# PCB_0_2.net
KiCad netlist of a schematic drawn in EAGLE
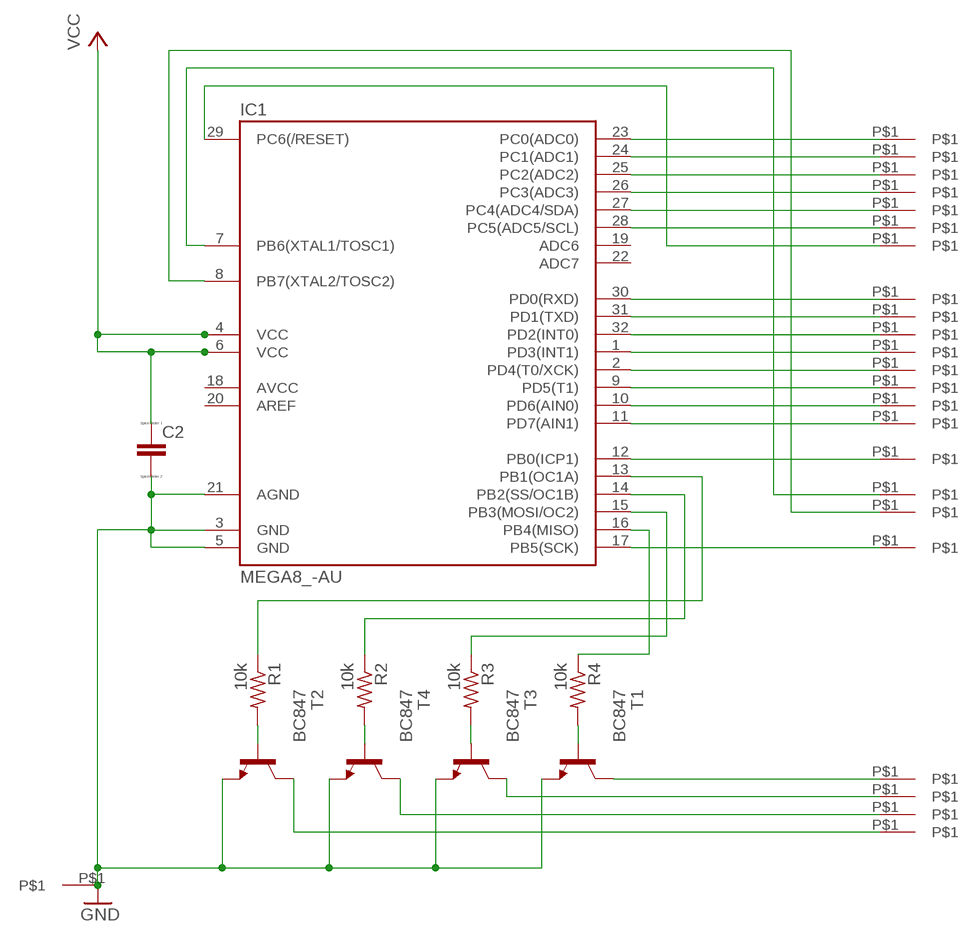
[diagram p0: schematic, sheet 1]

(export (version "E")
  (design (tool "Eeschema 10.0.6"))
  (components
    (comp (ref "C2")
      (value "C-EUC0603K")
      (footprint "eagle-import:C0603K")
      (libsource (lib "eagle-import") (part "C-EUC0603K"))
    )
    (comp (ref "IC1")
      (value "MEGA8_-AU")
      (footprint "eagle-import:TQFP32-08")
      (libsource (lib "eagle-import") (part "MEGA8_-AU"))
    )
    (comp (ref "PC0")
      (value "Fahrkanal")
      (footprint "eagle-import:PAD")
      (libsource (lib "eagle-import") (part "PAD"))
    )
    (comp (ref "PC1")
      (value "Fahrkanal")
      (footprint "eagle-import:PAD")
      (libsource (lib "eagle-import") (part "PAD"))
    )
    (comp (ref "PC2")
      (value "Fahrkanal")
      (footprint "eagle-import:PAD")
      (libsource (lib "eagle-import") (part "PAD"))
    )
    (comp (ref "PC3")
      (value "Fahrkanal")
      (footprint "eagle-import:PAD")
      (libsource (lib "eagle-import") (part "PAD"))
    )
    (comp (ref "PC4")
      (value "Fahrkanal")
      (footprint "eagle-import:PAD")
      (libsource (lib "eagle-import") (part "PAD"))
    )
    (comp (ref "PC5")
      (value "Fahrkanal")
      (footprint "eagle-import:PAD")
      (libsource (lib "eagle-import") (part "PAD"))
    )
    (comp (ref "R1")
      (value "10k")
      (footprint "eagle-import:R0402")
      (libsource (lib "eagle-import") (part "R-US_R0402"))
    )
    (comp (ref "R2")
      (value "10k")
      (footprint "eagle-import:R0402")
      (libsource (lib "eagle-import") (part "R-US_R0402"))
    )
    (comp (ref "R3")
      (value "10k")
      (footprint "eagle-import:R0402")
      (libsource (lib "eagle-import") (part "R-US_R0402"))
    )
    (comp (ref "R4")
      (value "10k")
      (footprint "eagle-import:R0402")
      (libsource (lib "eagle-import") (part "R-US_R0402"))
    )
    (comp (ref "T1")
      (value "BC847")
      (footprint "eagle-import:SOT23")
      (libsource (lib "eagle-import") (part "BC847"))
    )
    (comp (ref "T2")
      (value "BC847")
      (footprint "eagle-import:SOT23")
      (libsource (lib "eagle-import") (part "BC847"))
    )
    (comp (ref "T3")
      (value "BC847")
      (footprint "eagle-import:SOT23")
      (libsource (lib "eagle-import") (part "BC847"))
    )
    (comp (ref "T4")
      (value "BC847")
      (footprint "eagle-import:SOT23")
      (libsource (lib "eagle-import") (part "BC847"))
    )
    (comp (ref "U$1")
      (value "PAD")
      (footprint "eagle-import:PAD")
      (libsource (lib "eagle-import") (part "PAD"))
    )
    (comp (ref "U$2")
      (value "PAD")
      (footprint "eagle-import:PAD")
      (libsource (lib "eagle-import") (part "PAD"))
    )
    (comp (ref "U$3")
      (value "PAD")
      (footprint "eagle-import:PAD")
      (libsource (lib "eagle-import") (part "PAD"))
    )
    (comp (ref "U$4")
      (value "PAD")
      (footprint "eagle-import:PAD")
      (libsource (lib "eagle-import") (part "PAD"))
    )
    (comp (ref "U$5")
      (value "PAD")
      (footprint "eagle-import:PAD")
      (libsource (lib "eagle-import") (part "PAD"))
    )
    (comp (ref "U$6")
      (value "PAD")
      (footprint "eagle-import:PAD")
      (libsource (lib "eagle-import") (part "PAD"))
    )
    (comp (ref "U$7")
      (value "PAD")
      (footprint "eagle-import:PAD")
      (libsource (lib "eagle-import") (part "PAD"))
    )
    (comp (ref "U$8")
      (value "PAD")
      (footprint "eagle-import:PAD")
      (libsource (lib "eagle-import") (part "PAD"))
    )
    (comp (ref "U$9")
      (value "PAD")
      (footprint "eagle-import:PAD")
      (libsource (lib "eagle-import") (part "PAD"))
    )
    (comp (ref "U$10")
      (value "PAD")
      (footprint "eagle-import:PAD")
      (libsource (lib "eagle-import") (part "PAD"))
    )
    (comp (ref "U$11")
      (value "PAD")
      (footprint "eagle-import:PAD")
      (libsource (lib "eagle-import") (part "PAD"))
    )
    (comp (ref "U$12")
      (value "PAD")
      (footprint "eagle-import:PAD")
      (libsource (lib "eagle-import") (part "PAD"))
    )
    (comp (ref "U$14")
      (value "PAD")
      (footprint "eagle-import:PAD")
      (libsource (lib "eagle-import") (part "PAD"))
    )
    (comp (ref "U$15")
      (value "PAD")
      (footprint "eagle-import:PAD")
      (libsource (lib "eagle-import") (part "PAD"))
    )
    (comp (ref "U$16")
      (value "PAD")
      (footprint "eagle-import:PAD")
      (libsource (lib "eagle-import") (part "PAD"))
    )
    (comp (ref "U$17")
      (value "PAD")
      (footprint "eagle-import:PAD")
      (libsource (lib "eagle-import") (part "PAD"))
    )
    (comp (ref "U$18")
      (value "PAD")
      (footprint "eagle-import:PAD")
      (libsource (lib "eagle-import") (part "PAD"))
    )
    (comp (ref "U$19")
      (value "PAD")
      (footprint "eagle-import:PAD")
      (libsource (lib "eagle-import") (part "PAD"))
    )
  )
  (nets
    (net (code "1") (name "GND") (class "Default")
      (node (ref "C2") (pin "2") (pinfunction "2_2") (pintype "passive"))
      (node (ref "IC1") (pin "21") (pinfunction "AGND_21") (pintype "power_in"))
      (node (ref "IC1") (pin "3") (pinfunction "GND_3") (pintype "power_in"))
      (node (ref "IC1") (pin "5") (pinfunction "GND_5") (pintype "power_in"))
      (node (ref "PC5") (pin "P$1") (pinfunction "P$1_P$1") (pintype "bidirectional"))
      (node (ref "T1") (pin "2") (pinfunction "E_2") (pintype "passive"))
      (node (ref "T2") (pin "2") (pinfunction "E_2") (pintype "passive"))
      (node (ref "T3") (pin "2") (pinfunction "E_2") (pintype "passive"))
      (node (ref "T4") (pin "2") (pinfunction "E_2") (pintype "passive"))
    )
    (net (code "2") (name "Net-(IC1-PB0(ICP1))") (class "Default")
      (node (ref "IC1") (pin "12") (pinfunction "PB0(ICP1)_12") (pintype "bidirectional"))
      (node (ref "U$16") (pin "P$1") (pinfunction "P$1_P$1") (pintype "bidirectional"))
    )
    (net (code "3") (name "Net-(IC1-PB1(OC1A))") (class "Default")
      (node (ref "IC1") (pin "13") (pinfunction "PB1(OC1A)_13") (pintype "bidirectional"))
      (node (ref "R1") (pin "1") (pinfunction "1_1") (pintype "passive"))
    )
    (net (code "4") (name "Net-(IC1-PB2(SS{slash}OC1B))") (class "Default")
      (node (ref "IC1") (pin "14") (pinfunction "PB2(SS/OC1B)_14") (pintype "bidirectional"))
      (node (ref "R2") (pin "1") (pinfunction "1_1") (pintype "passive"))
    )
    (net (code "5") (name "Net-(IC1-PB3(MOSI{slash}OC2))") (class "Default")
      (node (ref "IC1") (pin "15") (pinfunction "PB3(MOSI/OC2)_15") (pintype "bidirectional"))
      (node (ref "R3") (pin "1") (pinfunction "1_1") (pintype "passive"))
    )
    (net (code "6") (name "Net-(IC1-PB4(MISO))") (class "Default")
      (node (ref "IC1") (pin "16") (pinfunction "PB4(MISO)_16") (pintype "bidirectional"))
      (node (ref "R4") (pin "1") (pinfunction "1_1") (pintype "passive"))
    )
    (net (code "7") (name "Net-(IC1-PB5(SCK))") (class "Default")
      (node (ref "IC1") (pin "17") (pinfunction "PB5(SCK)_17") (pintype "bidirectional"))
      (node (ref "U$19") (pin "P$1") (pinfunction "P$1_P$1") (pintype "bidirectional"))
    )
    (net (code "8") (name "Net-(IC1-PB6(XTAL1{slash}TOSC1))") (class "Default")
      (node (ref "IC1") (pin "7") (pinfunction "PB6(XTAL1/TOSC1)_7") (pintype "bidirectional"))
      (node (ref "U$17") (pin "P$1") (pinfunction "P$1_P$1") (pintype "bidirectional"))
    )
    (net (code "9") (name "Net-(IC1-PB7(XTAL2{slash}TOSC2))") (class "Default")
      (node (ref "IC1") (pin "8") (pinfunction "PB7(XTAL2/TOSC2)_8") (pintype "bidirectional"))
      (node (ref "U$18") (pin "P$1") (pinfunction "P$1_P$1") (pintype "bidirectional"))
    )
    (net (code "10") (name "Net-(IC1-PC0(ADC0))") (class "Default")
      (node (ref "IC1") (pin "23") (pinfunction "PC0(ADC0)_23") (pintype "bidirectional"))
      (node (ref "PC0") (pin "P$1") (pinfunction "P$1_P$1") (pintype "bidirectional"))
    )
    (net (code "11") (name "Net-(IC1-PC1(ADC1))") (class "Default")
      (node (ref "IC1") (pin "24") (pinfunction "PC1(ADC1)_24") (pintype "bidirectional"))
      (node (ref "U$2") (pin "P$1") (pinfunction "P$1_P$1") (pintype "bidirectional"))
    )
    (net (code "12") (name "Net-(IC1-PC2(ADC2))") (class "Default")
      (node (ref "IC1") (pin "25") (pinfunction "PC2(ADC2)_25") (pintype "bidirectional"))
      (node (ref "U$3") (pin "P$1") (pinfunction "P$1_P$1") (pintype "bidirectional"))
    )
    (net (code "13") (name "Net-(IC1-PC3(ADC3))") (class "Default")
      (node (ref "IC1") (pin "26") (pinfunction "PC3(ADC3)_26") (pintype "bidirectional"))
      (node (ref "U$4") (pin "P$1") (pinfunction "P$1_P$1") (pintype "bidirectional"))
    )
    (net (code "14") (name "Net-(IC1-PC4(ADC4{slash}SDA))") (class "Default")
      (node (ref "IC1") (pin "27") (pinfunction "PC4(ADC4/SDA)_27") (pintype "bidirectional"))
      (node (ref "U$5") (pin "P$1") (pinfunction "P$1_P$1") (pintype "bidirectional"))
    )
    (net (code "15") (name "Net-(IC1-PC5(ADC5{slash}SCL))") (class "Default")
      (node (ref "IC1") (pin "28") (pinfunction "PC5(ADC5/SCL)_28") (pintype "bidirectional"))
      (node (ref "U$6") (pin "P$1") (pinfunction "P$1_P$1") (pintype "bidirectional"))
    )
    (net (code "16") (name "Net-(IC1-PC6({slash}RESET))") (class "Default")
      (node (ref "IC1") (pin "29") (pinfunction "PC6(/RESET)_29") (pintype "bidirectional"))
      (node (ref "U$7") (pin "P$1") (pinfunction "P$1_P$1") (pintype "bidirectional"))
    )
    (net (code "17") (name "Net-(IC1-PD0(RXD))") (class "Default")
      (node (ref "IC1") (pin "30") (pinfunction "PD0(RXD)_30") (pintype "bidirectional"))
      (node (ref "U$8") (pin "P$1") (pinfunction "P$1_P$1") (pintype "bidirectional"))
    )
    (net (code "18") (name "Net-(IC1-PD1(TXD))") (class "Default")
      (node (ref "IC1") (pin "31") (pinfunction "PD1(TXD)_31") (pintype "bidirectional"))
      (node (ref "U$9") (pin "P$1") (pinfunction "P$1_P$1") (pintype "bidirectional"))
    )
    (net (code "19") (name "Net-(IC1-PD2(INT0))") (class "Default")
      (node (ref "IC1") (pin "32") (pinfunction "PD2(INT0)_32") (pintype "bidirectional"))
      (node (ref "U$10") (pin "P$1") (pinfunction "P$1_P$1") (pintype "bidirectional"))
    )
    (net (code "20") (name "Net-(IC1-PD3(INT1))") (class "Default")
      (node (ref "IC1") (pin "1") (pinfunction "PD3(INT1)_1") (pintype "bidirectional"))
      (node (ref "U$11") (pin "P$1") (pinfunction "P$1_P$1") (pintype "bidirectional"))
    )
    (net (code "21") (name "Net-(IC1-PD4(T0{slash}XCK))") (class "Default")
      (node (ref "IC1") (pin "2") (pinfunction "PD4(T0/XCK)_2") (pintype "bidirectional"))
      (node (ref "U$12") (pin "P$1") (pinfunction "P$1_P$1") (pintype "bidirectional"))
    )
    (net (code "22") (name "Net-(IC1-PD5(T1))") (class "Default")
      (node (ref "IC1") (pin "9") (pinfunction "PD5(T1)_9") (pintype "bidirectional"))
      (node (ref "U$1") (pin "P$1") (pinfunction "P$1_P$1") (pintype "bidirectional"))
    )
    (net (code "23") (name "Net-(IC1-PD6(AIN0))") (class "Default")
      (node (ref "IC1") (pin "10") (pinfunction "PD6(AIN0)_10") (pintype "bidirectional"))
      (node (ref "U$14") (pin "P$1") (pinfunction "P$1_P$1") (pintype "bidirectional"))
    )
    (net (code "24") (name "Net-(IC1-PD7(AIN1))") (class "Default")
      (node (ref "IC1") (pin "11") (pinfunction "PD7(AIN1)_11") (pintype "bidirectional"))
      (node (ref "U$15") (pin "P$1") (pinfunction "P$1_P$1") (pintype "bidirectional"))
    )
    (net (code "25") (name "Net-(T1-B)") (class "Default")
      (node (ref "R4") (pin "2") (pinfunction "2_2") (pintype "passive"))
      (node (ref "T1") (pin "1") (pinfunction "B_1") (pintype "passive"))
    )
    (net (code "26") (name "Net-(T1-C)") (class "Default")
      (node (ref "PC1") (pin "P$1") (pinfunction "P$1_P$1") (pintype "bidirectional"))
      (node (ref "T1") (pin "3") (pinfunction "C_3") (pintype "passive"))
    )
    (net (code "27") (name "Net-(T2-B)") (class "Default")
      (node (ref "R1") (pin "2") (pinfunction "2_2") (pintype "passive"))
      (node (ref "T2") (pin "1") (pinfunction "B_1") (pintype "passive"))
    )
    (net (code "28") (name "Net-(T2-C)") (class "Default")
      (node (ref "PC4") (pin "P$1") (pinfunction "P$1_P$1") (pintype "bidirectional"))
      (node (ref "T2") (pin "3") (pinfunction "C_3") (pintype "passive"))
    )
    (net (code "29") (name "Net-(T3-B)") (class "Default")
      (node (ref "R3") (pin "2") (pinfunction "2_2") (pintype "passive"))
      (node (ref "T3") (pin "1") (pinfunction "B_1") (pintype "passive"))
    )
    (net (code "30") (name "Net-(T3-C)") (class "Default")
      (node (ref "PC2") (pin "P$1") (pinfunction "P$1_P$1") (pintype "bidirectional"))
      (node (ref "T3") (pin "3") (pinfunction "C_3") (pintype "passive"))
    )
    (net (code "31") (name "Net-(T4-B)") (class "Default")
      (node (ref "R2") (pin "2") (pinfunction "2_2") (pintype "passive"))
      (node (ref "T4") (pin "1") (pinfunction "B_1") (pintype "passive"))
    )
    (net (code "32") (name "Net-(T4-C)") (class "Default")
      (node (ref "PC3") (pin "P$1") (pinfunction "P$1_P$1") (pintype "bidirectional"))
      (node (ref "T4") (pin "3") (pinfunction "C_3") (pintype "passive"))
    )
    (net (code "33") (name "VCC") (class "Default")
      (node (ref "C2") (pin "1") (pinfunction "1_1") (pintype "passive"))
      (node (ref "IC1") (pin "4") (pinfunction "VCC_4") (pintype "power_in"))
      (node (ref "IC1") (pin "6") (pinfunction "VCC_6") (pintype "power_in"))
    )
    (net (code "34") (name "unconnected-(IC1-ADC6-Pad19)") (class "Default")
      (node (ref "IC1") (pin "19") (pinfunction "ADC6_19") (pintype "passive"))
    )
    (net (code "35") (name "unconnected-(IC1-ADC7-Pad22)") (class "Default")
      (node (ref "IC1") (pin "22") (pinfunction "ADC7_22") (pintype "passive"))
    )
    (net (code "36") (name "unconnected-(IC1-AREF-Pad20)") (class "Default")
      (node (ref "IC1") (pin "20") (pinfunction "AREF_20") (pintype "passive"))
    )
    (net (code "37") (name "unconnected-(IC1-AVCC-Pad18)") (class "Default")
      (node (ref "IC1") (pin "18") (pinfunction "AVCC_18") (pintype "passive"))
    )
  )
)
